# 4_valve_front_connect.net
KiCad netlist of a schematic drawn in EAGLE
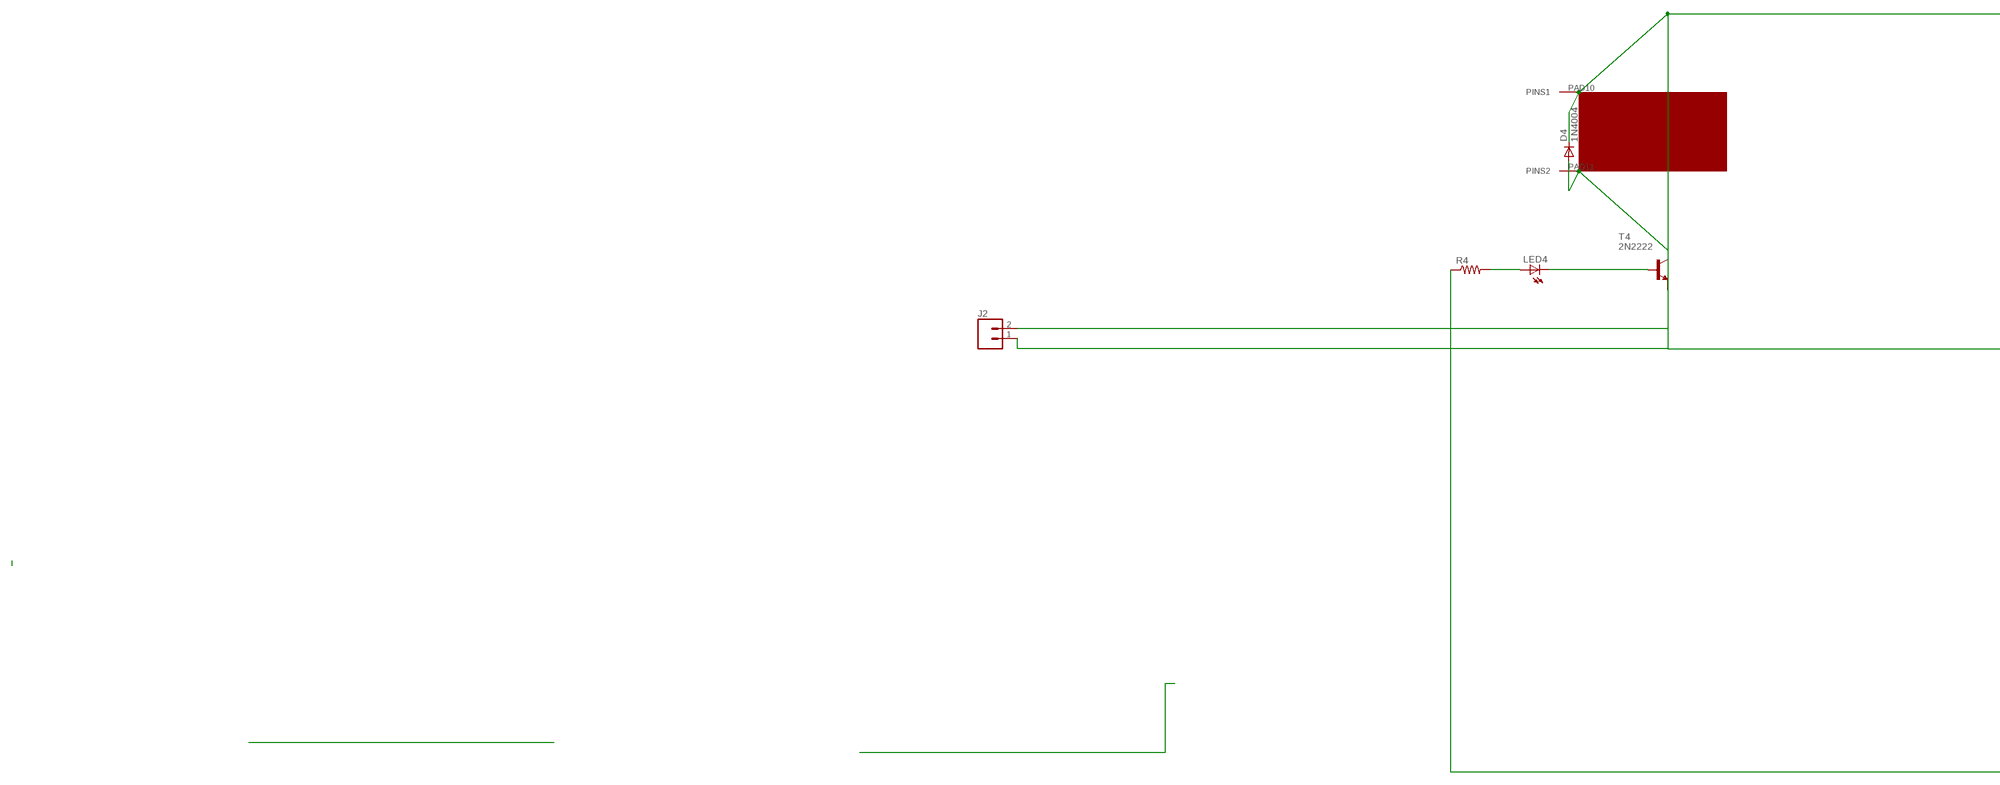
[diagram p0: schematic, sheet 1, part 1 of 2]
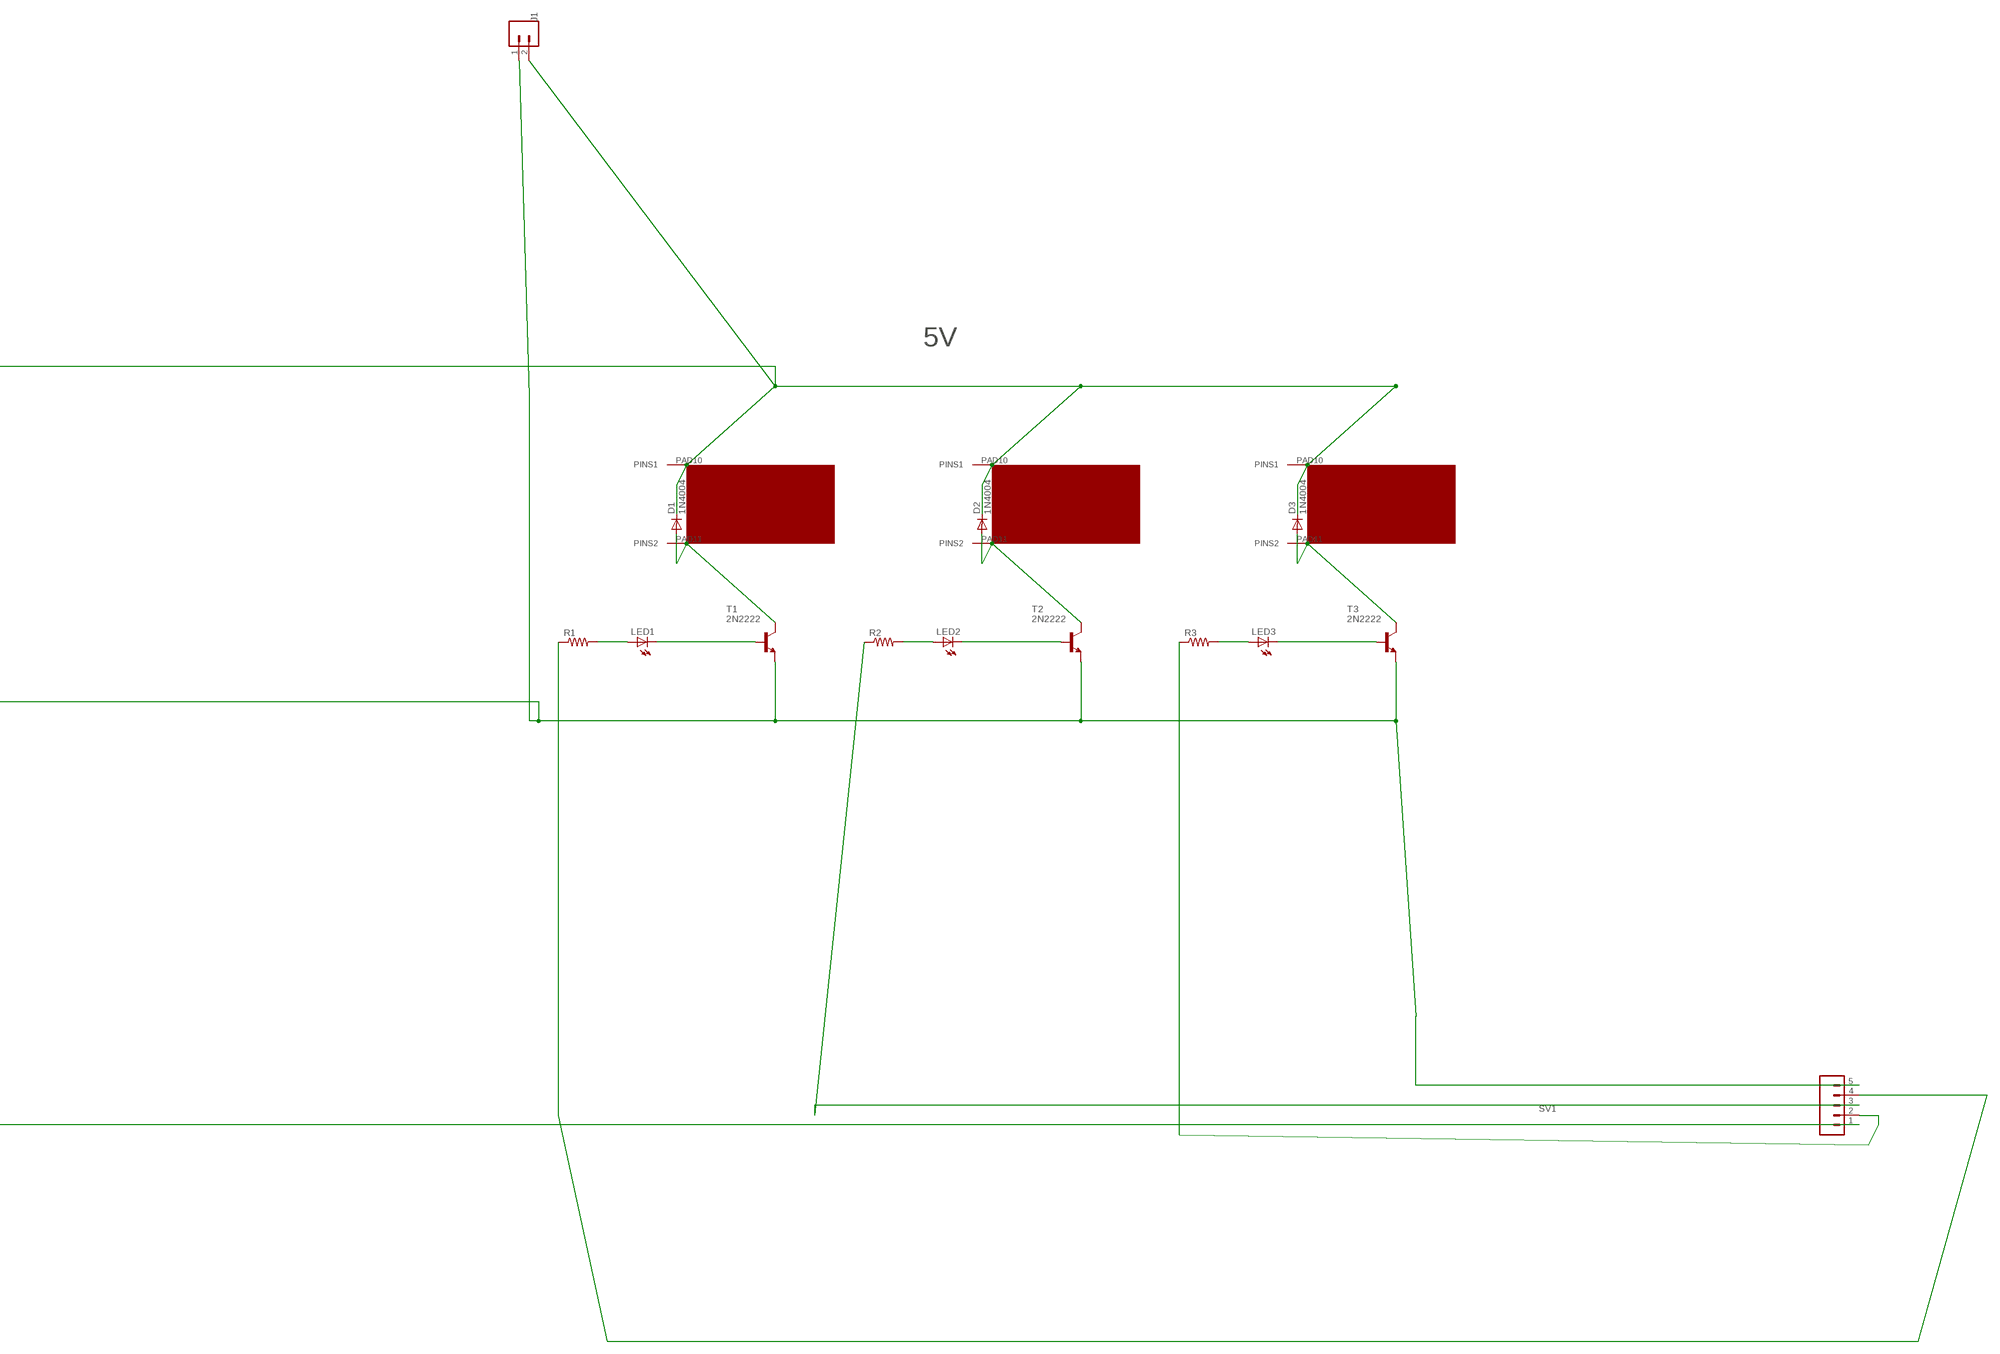
[diagram p1: schematic, sheet 1, part 2 of 2]

(export (version "E")
  (design (tool "Eeschema 10.0.6"))
  (components
    (comp (ref "D1")
      (value "1N4004")
      (footprint "eagle-import:DO41-10")
      (libsource (lib "eagle-import") (part "1N4004"))
    )
    (comp (ref "D2")
      (value "1N4004")
      (footprint "eagle-import:DO41-10")
      (libsource (lib "eagle-import") (part "1N4004"))
    )
    (comp (ref "D3")
      (value "1N4004")
      (footprint "eagle-import:DO41-10")
      (libsource (lib "eagle-import") (part "1N4004"))
    )
    (comp (ref "D4")
      (value "1N4004")
      (footprint "eagle-import:DO41-10")
      (libsource (lib "eagle-import") (part "1N4004"))
    )
    (comp (ref "J1")
      (value "CONN_023.5MM")
      (footprint "eagle-import:SCREWTERMINAL-3.5MM-2")
      (libsource (lib "eagle-import") (part "CONN_023.5MM"))
    )
    (comp (ref "J2")
      (value "CONN_02")
      (footprint "eagle-import:1X02")
      (libsource (lib "eagle-import") (part "CONN_02"))
    )
    (comp (ref "LED1")
      (value "LED5MM")
      (footprint "eagle-import:LED5MM")
      (libsource (lib "eagle-import") (part "LED5MM"))
    )
    (comp (ref "LED2")
      (value "LED5MM")
      (footprint "eagle-import:LED5MM")
      (libsource (lib "eagle-import") (part "LED5MM"))
    )
    (comp (ref "LED3")
      (value "LED5MM")
      (footprint "eagle-import:LED5MM")
      (libsource (lib "eagle-import") (part "LED5MM"))
    )
    (comp (ref "LED4")
      (value "LED5MM")
      (footprint "eagle-import:LED5MM")
      (libsource (lib "eagle-import") (part "LED5MM"))
    )
    (comp (ref "R1")
      (value "R-US_0207/10")
      (footprint "eagle-import:0207_10")
      (libsource (lib "eagle-import") (part "R-US_0207/10"))
    )
    (comp (ref "R2")
      (value "R-US_0207/10")
      (footprint "eagle-import:0207_10")
      (libsource (lib "eagle-import") (part "R-US_0207/10"))
    )
    (comp (ref "R3")
      (value "R-US_0207/10")
      (footprint "eagle-import:0207_10")
      (libsource (lib "eagle-import") (part "R-US_0207/10"))
    )
    (comp (ref "R4")
      (value "R-US_0207/10")
      (footprint "eagle-import:0207_10")
      (libsource (lib "eagle-import") (part "R-US_0207/10"))
    )
    (comp (ref "SV1")
      (value "CONN_05")
      (footprint "eagle-import:1X05")
      (libsource (lib "eagle-import") (part "CONN_05"))
    )
    (comp (ref "T1")
      (value "2N2222")
      (footprint "eagle-import:TO92-EBC-OVAL")
      (libsource (lib "eagle-import") (part "2N2222"))
    )
    (comp (ref "T2")
      (value "2N2222")
      (footprint "eagle-import:TO92-EBC-OVAL")
      (libsource (lib "eagle-import") (part "2N2222"))
    )
    (comp (ref "T3")
      (value "2N2222")
      (footprint "eagle-import:TO92-EBC-OVAL")
      (libsource (lib "eagle-import") (part "2N2222"))
    )
    (comp (ref "T4")
      (value "2N2222")
      (footprint "eagle-import:TO92-EBC-OVAL")
      (libsource (lib "eagle-import") (part "2N2222"))
    )
    (comp (ref "U$1")
      (value "VALVE")
      (footprint "eagle-import:VALVTEST2")
      (libsource (lib "eagle-import") (part "VALVE"))
    )
    (comp (ref "U$2")
      (value "VALVE")
      (footprint "eagle-import:VALVTEST2")
      (libsource (lib "eagle-import") (part "VALVE"))
    )
    (comp (ref "U$3")
      (value "VALVE")
      (footprint "eagle-import:VALVTEST2")
      (libsource (lib "eagle-import") (part "VALVE"))
    )
    (comp (ref "VALVE3")
      (value "VALVE")
      (footprint "eagle-import:VALVTEST2")
      (libsource (lib "eagle-import") (part "VALVE"))
    )
  )
  (nets
    (net (code "1") (name "/5V") (class "Default")
      (node (ref "D1") (pin "C") (pinfunction "C_C") (pintype "passive"))
      (node (ref "D2") (pin "C") (pinfunction "C_C") (pintype "passive"))
      (node (ref "D3") (pin "C") (pinfunction "C_C") (pintype "passive"))
      (node (ref "D4") (pin "C") (pinfunction "C_C") (pintype "passive"))
      (node (ref "J1") (pin "2") (pinfunction "2_2") (pintype "passive"))
      (node (ref "J2") (pin "2") (pinfunction "2_2") (pintype "passive"))
      (node (ref "U$1") (pin "PAD10") (pinfunction "PINS1_PAD10") (pintype "bidirectional"))
      (node (ref "U$2") (pin "PAD10") (pinfunction "PINS1_PAD10") (pintype "bidirectional"))
      (node (ref "U$3") (pin "PAD10") (pinfunction "PINS1_PAD10") (pintype "bidirectional"))
      (node (ref "VALVE3") (pin "PAD10") (pinfunction "PINS1_PAD10") (pintype "bidirectional"))
    )
    (net (code "2") (name "Net-(J1-Pad1)") (class "Default")
      (node (ref "J1") (pin "1") (pinfunction "1_1") (pintype "passive"))
      (node (ref "J2") (pin "1") (pinfunction "1_1") (pintype "passive"))
      (node (ref "SV1") (pin "5") (pinfunction "5_5") (pintype "passive"))
      (node (ref "T1") (pin "E") (pinfunction "E_E") (pintype "passive"))
      (node (ref "T2") (pin "E") (pinfunction "E_E") (pintype "passive"))
      (node (ref "T3") (pin "E") (pinfunction "E_E") (pintype "passive"))
      (node (ref "T4") (pin "E") (pinfunction "E_E") (pintype "passive"))
    )
    (net (code "3") (name "Net-(LED1-C)") (class "Default")
      (node (ref "LED1") (pin "K") (pinfunction "C_K") (pintype "passive"))
      (node (ref "T1") (pin "B") (pinfunction "B_B") (pintype "passive"))
    )
    (net (code "4") (name "Net-(LED1-PadA)") (class "Default")
      (node (ref "LED1") (pin "A") (pinfunction "A_A") (pintype "passive"))
      (node (ref "R1") (pin "2") (pinfunction "2_2") (pintype "passive"))
    )
    (net (code "5") (name "Net-(LED2-C)") (class "Default")
      (node (ref "LED2") (pin "K") (pinfunction "C_K") (pintype "passive"))
      (node (ref "T2") (pin "B") (pinfunction "B_B") (pintype "passive"))
    )
    (net (code "6") (name "Net-(LED2-PadA)") (class "Default")
      (node (ref "LED2") (pin "A") (pinfunction "A_A") (pintype "passive"))
      (node (ref "R2") (pin "2") (pinfunction "2_2") (pintype "passive"))
    )
    (net (code "7") (name "Net-(LED3-C)") (class "Default")
      (node (ref "LED3") (pin "K") (pinfunction "C_K") (pintype "passive"))
      (node (ref "T3") (pin "B") (pinfunction "B_B") (pintype "passive"))
    )
    (net (code "8") (name "Net-(LED3-PadA)") (class "Default")
      (node (ref "LED3") (pin "A") (pinfunction "A_A") (pintype "passive"))
      (node (ref "R3") (pin "2") (pinfunction "2_2") (pintype "passive"))
    )
    (net (code "9") (name "Net-(LED4-C)") (class "Default")
      (node (ref "LED4") (pin "K") (pinfunction "C_K") (pintype "passive"))
      (node (ref "T4") (pin "B") (pinfunction "B_B") (pintype "passive"))
    )
    (net (code "10") (name "Net-(LED4-PadA)") (class "Default")
      (node (ref "LED4") (pin "A") (pinfunction "A_A") (pintype "passive"))
      (node (ref "R4") (pin "2") (pinfunction "2_2") (pintype "passive"))
    )
    (net (code "11") (name "Net-(R1-Pad1)") (class "Default")
      (node (ref "R1") (pin "1") (pinfunction "1_1") (pintype "passive"))
      (node (ref "SV1") (pin "4") (pinfunction "4_4") (pintype "passive"))
    )
    (net (code "12") (name "Net-(R2-Pad1)") (class "Default")
      (node (ref "R2") (pin "1") (pinfunction "1_1") (pintype "passive"))
      (node (ref "SV1") (pin "3") (pinfunction "3_3") (pintype "passive"))
    )
    (net (code "13") (name "Net-(R3-Pad1)") (class "Default")
      (node (ref "R3") (pin "1") (pinfunction "1_1") (pintype "passive"))
      (node (ref "SV1") (pin "2") (pinfunction "2_2") (pintype "passive"))
    )
    (net (code "14") (name "Net-(R4-Pad1)") (class "Default")
      (node (ref "R4") (pin "1") (pinfunction "1_1") (pintype "passive"))
      (node (ref "SV1") (pin "1") (pinfunction "1_1") (pintype "passive"))
    )
    (net (code "15") (name "Net-(U$1-PINS2)") (class "Default")
      (node (ref "D1") (pin "A") (pinfunction "A_A") (pintype "passive"))
      (node (ref "T1") (pin "C") (pinfunction "C_C") (pintype "passive"))
      (node (ref "U$1") (pin "PAD11") (pinfunction "PINS2_PAD11") (pintype "bidirectional"))
    )
    (net (code "16") (name "Net-(U$2-PINS2)") (class "Default")
      (node (ref "D2") (pin "A") (pinfunction "A_A") (pintype "passive"))
      (node (ref "T2") (pin "C") (pinfunction "C_C") (pintype "passive"))
      (node (ref "U$2") (pin "PAD11") (pinfunction "PINS2_PAD11") (pintype "bidirectional"))
    )
    (net (code "17") (name "Net-(U$3-PINS2)") (class "Default")
      (node (ref "D4") (pin "A") (pinfunction "A_A") (pintype "passive"))
      (node (ref "T4") (pin "C") (pinfunction "C_C") (pintype "passive"))
      (node (ref "U$3") (pin "PAD11") (pinfunction "PINS2_PAD11") (pintype "bidirectional"))
    )
    (net (code "18") (name "Net-(VALVE3-PINS2)") (class "Default")
      (node (ref "D3") (pin "A") (pinfunction "A_A") (pintype "passive"))
      (node (ref "T3") (pin "C") (pinfunction "C_C") (pintype "passive"))
      (node (ref "VALVE3") (pin "PAD11") (pinfunction "PINS2_PAD11") (pintype "bidirectional"))
    )
  )
)
